# snes-breakout.net
KiCad netlist of a schematic drawn in EAGLE
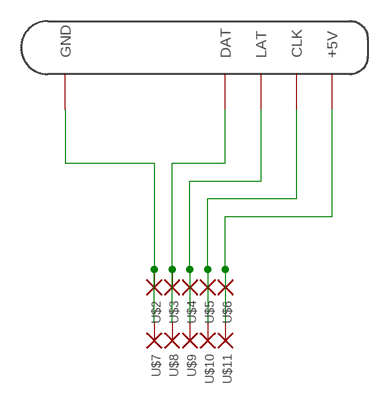
[diagram p0: schematic, sheet 1]

(export (version "E")
  (design (tool "Eeschema 10.0.6"))
  (components
    (comp (ref "U$1")
      (value "SNES-CONNECTOR")
      (footprint "eagle-import:SNES-CONNECTOR")
      (libsource (lib "eagle-import") (part "SNES-CONNECTOR"))
    )
    (comp (ref "U$2")
      (value "SMDPADSMD6080")
      (footprint "eagle-import:SMD6080")
      (libsource (lib "eagle-import") (part "SMDPADSMD6080"))
    )
    (comp (ref "U$3")
      (value "SMDPADSMD6080")
      (footprint "eagle-import:SMD6080")
      (libsource (lib "eagle-import") (part "SMDPADSMD6080"))
    )
    (comp (ref "U$4")
      (value "SMDPADSMD6080")
      (footprint "eagle-import:SMD6080")
      (libsource (lib "eagle-import") (part "SMDPADSMD6080"))
    )
    (comp (ref "U$5")
      (value "SMDPADSMD6080")
      (footprint "eagle-import:SMD6080")
      (libsource (lib "eagle-import") (part "SMDPADSMD6080"))
    )
    (comp (ref "U$6")
      (value "SMDPADSMD6080")
      (footprint "eagle-import:SMD6080")
      (libsource (lib "eagle-import") (part "SMDPADSMD6080"))
    )
    (comp (ref "U$7")
      (value "SMDPADSMD6080")
      (footprint "eagle-import:SMD6080")
      (libsource (lib "eagle-import") (part "SMDPADSMD6080"))
    )
    (comp (ref "U$8")
      (value "SMDPADSMD6080")
      (footprint "eagle-import:SMD6080")
      (libsource (lib "eagle-import") (part "SMDPADSMD6080"))
    )
    (comp (ref "U$9")
      (value "SMDPADSMD6080")
      (footprint "eagle-import:SMD6080")
      (libsource (lib "eagle-import") (part "SMDPADSMD6080"))
    )
    (comp (ref "U$10")
      (value "SMDPADSMD6080")
      (footprint "eagle-import:SMD6080")
      (libsource (lib "eagle-import") (part "SMDPADSMD6080"))
    )
    (comp (ref "U$11")
      (value "SMDPADSMD6080")
      (footprint "eagle-import:SMD6080")
      (libsource (lib "eagle-import") (part "SMDPADSMD6080"))
    )
  )
  (nets
    (net (code "1") (name "Net-(U$1-+5V)") (class "Default")
      (node (ref "U$1") (pin "P$7") (pinfunction "+5V_P$7") (pintype "bidirectional"))
      (node (ref "U$11") (pin "P$1") (pinfunction "P_P$1") (pintype "passive"))
      (node (ref "U$6") (pin "P$1") (pinfunction "P_P$1") (pintype "passive"))
    )
    (net (code "2") (name "Net-(U$1-CLK)") (class "Default")
      (node (ref "U$1") (pin "P$6") (pinfunction "CLK_P$6") (pintype "bidirectional"))
      (node (ref "U$10") (pin "P$1") (pinfunction "P_P$1") (pintype "passive"))
      (node (ref "U$5") (pin "P$1") (pinfunction "P_P$1") (pintype "passive"))
    )
    (net (code "3") (name "Net-(U$1-DAT)") (class "Default")
      (node (ref "U$1") (pin "P$4") (pinfunction "DAT_P$4") (pintype "bidirectional"))
      (node (ref "U$3") (pin "P$1") (pinfunction "P_P$1") (pintype "passive"))
      (node (ref "U$8") (pin "P$1") (pinfunction "P_P$1") (pintype "passive"))
    )
    (net (code "4") (name "Net-(U$1-GND)") (class "Default")
      (node (ref "U$1") (pin "P$1") (pinfunction "GND_P$1") (pintype "bidirectional"))
      (node (ref "U$2") (pin "P$1") (pinfunction "P_P$1") (pintype "passive"))
      (node (ref "U$7") (pin "P$1") (pinfunction "P_P$1") (pintype "passive"))
    )
    (net (code "5") (name "Net-(U$1-LAT)") (class "Default")
      (node (ref "U$1") (pin "P$5") (pinfunction "LAT_P$5") (pintype "bidirectional"))
      (node (ref "U$4") (pin "P$1") (pinfunction "P_P$1") (pintype "passive"))
      (node (ref "U$9") (pin "P$1") (pinfunction "P_P$1") (pintype "passive"))
    )
  )
)
